# MCU.net
KiCad netlist of a schematic drawn in Altium Designer
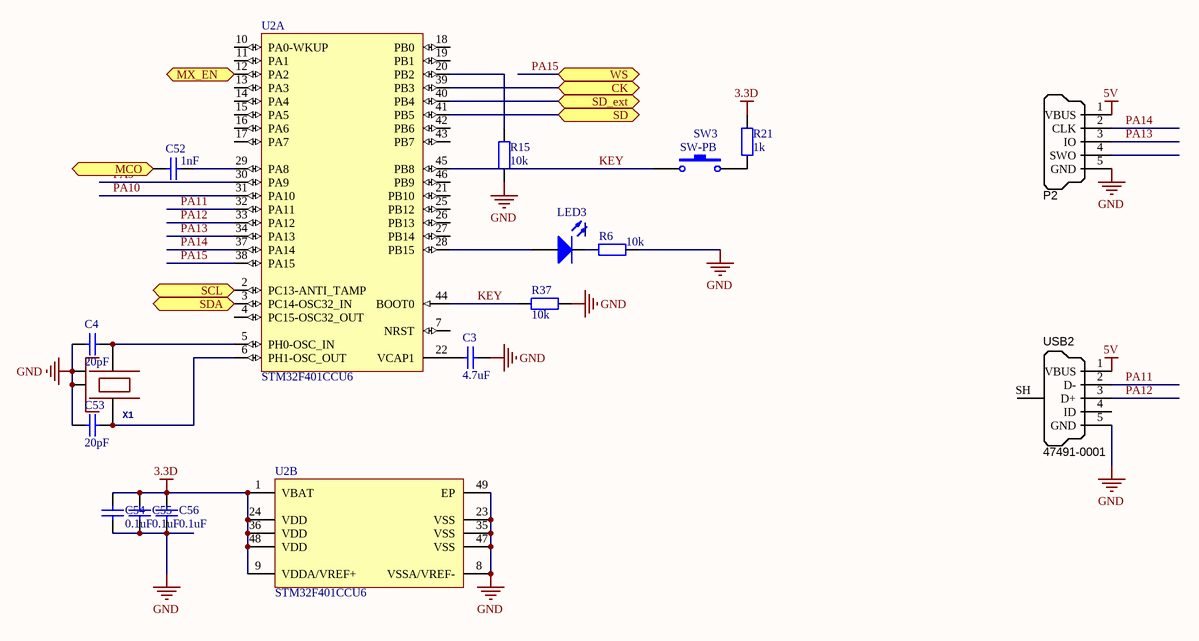
[diagram p0: MCU.SchDoc]

(export (version "E")
  (design (tool "Eeschema 10.0.6"))
  (components
    (comp (ref "C3")
      (value "4.7uF")
      (footprint "0603L")
      (description "Capacitor")
      (fields (field (name "Comment") "Cap") (field (name "PUBLISHER") "Altium Limited"))
      (libsource (lib "RTC6705") (part "Cap"))
    )
    (comp (ref "C4")
      (value "20pF")
      (footprint "0402")
      (description "Capacitor")
      (fields (field (name "Comment") "Cap") (field (name "PUBLISHER") "Altium Limited"))
      (libsource (lib "RTC6705") (part "Cap"))
    )
    (comp (ref "C52")
      (value "1nF")
      (footprint "0402")
      (description "Capacitor")
      (libsource (lib "RTC6705") (part "Cap"))
    )
    (comp (ref "C53")
      (value "20pF")
      (footprint "0402")
      (description "Capacitor")
      (fields (field (name "Comment") "Cap") (field (name "PUBLISHER") "Altium Limited"))
      (libsource (lib "RTC6705") (part "Cap"))
    )
    (comp (ref "C54")
      (value "0.1uF")
      (footprint "0402")
      (description "Capacitor")
      (fields (field (name "Comment") "Cap") (field (name "PUBLISHER") "Altium Limited"))
      (libsource (lib "RTC6705") (part "Cap"))
    )
    (comp (ref "C55")
      (value "0.1uF")
      (footprint "0402")
      (description "Capacitor")
      (fields (field (name "Comment") "Cap") (field (name "PUBLISHER") "Altium Limited"))
      (libsource (lib "RTC6705") (part "Cap"))
    )
    (comp (ref "C56")
      (value "0.1uF")
      (footprint "0402")
      (description "Capacitor")
      (fields (field (name "Comment") "Cap") (field (name "PUBLISHER") "Altium Limited"))
      (libsource (lib "RTC6705") (part "Cap"))
    )
    (comp (ref "LED3")
      (value "LED0")
      (footprint "0603")
      (description "Typical INFRARED GaAs LED")
      (fields (field (name "PUBLISHER") "Altium Limited"))
      (libsource (lib "Miscellaneous Devices") (part "LED0"))
    )
    (comp (ref "P2")
      (value "SWD_MicroUSB")
      (footprint "MICRO-YZX")
      (description "Connector SMD USB Micro Type B middle mount")
      (libsource (lib "sch") (part "SWD_MicroUSB"))
    )
    (comp (ref "R6")
      (value "10k")
      (footprint "0402")
      (description "Resistor")
      (fields (field (name "PUBLISHER") "Altium Limited"))
      (libsource (lib "Miscellaneous Devices") (part "Res2"))
    )
    (comp (ref "R15")
      (value "10k")
      (footprint "0402")
      (description "Resistor")
      (fields (field (name "PUBLISHER") "Altium Limited"))
      (libsource (lib "") (part "Res2_1"))
    )
    (comp (ref "R21")
      (value "1k")
      (footprint "0402")
      (description "Resistor")
      (fields (field (name "PUBLISHER") "Altium Limited"))
      (libsource (lib "") (part "Res2_2"))
    )
    (comp (ref "R37")
      (value "10k")
      (footprint "0402")
      (description "Resistor")
      (fields (field (name "Comment") "Res2") (field (name "PUBLISHER") "Altium Limited"))
      (libsource (lib "RTC6705") (part "Res2"))
    )
    (comp (ref "SW3")
      (value "SW-PB")
      (footprint "SW3x4")
      (description "Switch")
      (fields (field (name "PUBLISHER") "Altium Limited"))
      (libsource (lib "Miscellaneous Devices") (part "SW-PB"))
    )
    (comp (ref "U2")
      (value "STM32F401CCU6")
      (footprint "STM-UFQFPN48_N")
      (fields (field (name "MANUFACTURER") "STMicroelectronics"))
      (libsource (lib "STMicroelectronics STM32 F4") (part "STM32F401CCU6"))
    )
    (comp (ref "USB2")
      (value "USB Micro Type B")
      (footprint "MICRO-YZX")
      (description "Connector SMD USB Micro Type B middle mount")
      (fields (field (name "MANUFACTURER PART NUMBER 1") "47491-0001"))
      (libsource (lib "PBL - Connectors") (part "USB_Micro_TypeB"))
    )
    (comp (ref "X1")
      (value "24.000 KHz 3.2x2.5mm 8-10pf")
      (footprint "OSCILLATOR-2.5x2.0")
      (description "Crystal Oscillator in 3.2x2.5 SMD")
      (libsource (lib "pixhawk2") (part "OSCILLATOR-3.2X2.5"))
    )
  )
  (nets
    (net (code "1") (name "/CK") (class "Default")
      (node (ref "U2") (pin "39") (pinfunction "PB3_39") (pintype "bidirectional"))
    )
    (net (code "2") (name "/KEY") (class "Default")
      (node (ref "R37") (pin "1") (pinfunction "1_1") (pintype "passive"))
      (node (ref "SW3") (pin "1") (pinfunction "1_1") (pintype "passive"))
      (node (ref "U2") (pin "44") (pinfunction "BOOT0_44") (pintype "input"))
      (node (ref "U2") (pin "45") (pinfunction "PB8_45") (pintype "bidirectional"))
    )
    (net (code "3") (name "/MCO") (class "Default")
      (node (ref "C52") (pin "1") (pinfunction "1_1") (pintype "passive"))
    )
    (net (code "4") (name "/MX_EN") (class "Default")
      (node (ref "U2") (pin "12") (pinfunction "PA2_12") (pintype "bidirectional"))
    )
    (net (code "5") (name "/PA9") (class "Default")
      (node (ref "U2") (pin "30") (pinfunction "PA9_30") (pintype "bidirectional"))
    )
    (net (code "6") (name "/PA10") (class "Default")
      (node (ref "U2") (pin "31") (pinfunction "PA10_31") (pintype "bidirectional"))
    )
    (net (code "7") (name "/PA11") (class "Default")
      (node (ref "U2") (pin "32") (pinfunction "PA11_32") (pintype "bidirectional"))
      (node (ref "USB2") (pin "2") (pinfunction "D-_2") (pintype "passive"))
    )
    (net (code "8") (name "/PA12") (class "Default")
      (node (ref "U2") (pin "33") (pinfunction "PA12_33") (pintype "bidirectional"))
      (node (ref "USB2") (pin "3") (pinfunction "D+_3") (pintype "passive"))
    )
    (net (code "9") (name "/PA13") (class "Default")
      (node (ref "P2") (pin "3") (pinfunction "IO_3") (pintype "passive"))
      (node (ref "U2") (pin "34") (pinfunction "PA13_34") (pintype "bidirectional"))
    )
    (net (code "10") (name "/PA14") (class "Default")
      (node (ref "P2") (pin "2") (pinfunction "CLK_2") (pintype "passive"))
      (node (ref "U2") (pin "37") (pinfunction "PA14_37") (pintype "bidirectional"))
    )
    (net (code "11") (name "/PA15") (class "Default")
      (node (ref "U2") (pin "38") (pinfunction "PA15_38") (pintype "bidirectional"))
    )
    (net (code "12") (name "/SCL") (class "Default")
      (node (ref "U2") (pin "2") (pinfunction "PC13-ANTI_TAMP_2") (pintype "bidirectional"))
    )
    (net (code "13") (name "/SD") (class "Default")
      (node (ref "U2") (pin "41") (pinfunction "PB5_41") (pintype "bidirectional"))
    )
    (net (code "14") (name "/SDA") (class "Default")
      (node (ref "U2") (pin "3") (pinfunction "PC14-OSC32_IN_3") (pintype "bidirectional"))
    )
    (net (code "15") (name "/SD_ext") (class "Default")
      (node (ref "U2") (pin "40") (pinfunction "PB4_40") (pintype "bidirectional"))
    )
    (net (code "16") (name "3.3D") (class "Default")
      (node (ref "C54") (pin "2") (pinfunction "2_2") (pintype "passive"))
      (node (ref "C55") (pin "2") (pinfunction "2_2") (pintype "passive"))
      (node (ref "C56") (pin "2") (pinfunction "2_2") (pintype "passive"))
      (node (ref "R21") (pin "2") (pinfunction "2_2") (pintype "passive"))
      (node (ref "U2") (pin "1") (pinfunction "VBAT_1") (pintype "power_in"))
      (node (ref "U2") (pin "24") (pinfunction "VDD_24") (pintype "power_in"))
      (node (ref "U2") (pin "36") (pinfunction "VDD_36") (pintype "power_in"))
      (node (ref "U2") (pin "48") (pinfunction "VDD_48") (pintype "power_in"))
      (node (ref "U2") (pin "9") (pinfunction "VDDA/VREF+_9") (pintype "power_in"))
    )
    (net (code "17") (name "5V") (class "Default")
      (node (ref "P2") (pin "1") (pinfunction "VBUS_1") (pintype "passive"))
      (node (ref "USB2") (pin "1") (pinfunction "VBUS_1") (pintype "passive"))
    )
    (net (code "18") (name "GND") (class "Default")
      (node (ref "C3") (pin "1") (pinfunction "1_1") (pintype "passive"))
      (node (ref "C4") (pin "1") (pinfunction "1_1") (pintype "passive"))
      (node (ref "C53") (pin "1") (pinfunction "1_1") (pintype "passive"))
      (node (ref "C54") (pin "1") (pinfunction "1_1") (pintype "passive"))
      (node (ref "C55") (pin "1") (pinfunction "1_1") (pintype "passive"))
      (node (ref "C56") (pin "1") (pinfunction "1_1") (pintype "passive"))
      (node (ref "P2") (pin "5") (pinfunction "GND_5") (pintype "passive"))
      (node (ref "R15") (pin "2") (pinfunction "2_2") (pintype "passive"))
      (node (ref "R37") (pin "2") (pinfunction "2_2") (pintype "passive"))
      (node (ref "R6") (pin "2") (pinfunction "2_2") (pintype "passive"))
      (node (ref "U2") (pin "23") (pinfunction "VSS_23") (pintype "power_in"))
      (node (ref "U2") (pin "35") (pinfunction "VSS_35") (pintype "power_in"))
      (node (ref "U2") (pin "47") (pinfunction "VSS_47") (pintype "power_in"))
      (node (ref "U2") (pin "49") (pinfunction "EP_49") (pintype "power_in"))
      (node (ref "U2") (pin "8") (pinfunction "VSSA/VREF-_8") (pintype "power_in"))
      (node (ref "USB2") (pin "5") (pinfunction "GND_5") (pintype "passive"))
      (node (ref "X1") (pin "2") (pinfunction "NC_2_2") (pintype "open_emitter"))
      (node (ref "X1") (pin "4") (pinfunction "NC_4_4") (pintype "open_emitter"))
    )
    (net (code "19") (name "Net-(LED3-A)") (class "Default")
      (node (ref "LED3") (pin "1") (pinfunction "A_1") (pintype "passive"))
      (node (ref "U2") (pin "28") (pinfunction "PB15_28") (pintype "bidirectional"))
    )
    (net (code "20") (name "Net-(LED3-K)") (class "Default")
      (node (ref "LED3") (pin "2") (pinfunction "K_2") (pintype "passive"))
      (node (ref "R6") (pin "1") (pinfunction "1_1") (pintype "passive"))
    )
    (net (code "21") (name "Net-(R21-Pad1)") (class "Default")
      (node (ref "R21") (pin "1") (pinfunction "1_1") (pintype "passive"))
      (node (ref "SW3") (pin "2") (pinfunction "2_2") (pintype "passive"))
    )
    (net (code "22") (name "Net-(U2A-PA8)") (class "Default")
      (node (ref "C52") (pin "2") (pinfunction "2_2") (pintype "passive"))
      (node (ref "U2") (pin "29") (pinfunction "PA8_29") (pintype "bidirectional"))
    )
    (net (code "23") (name "Net-(U2A-PB2)") (class "Default")
      (node (ref "R15") (pin "1") (pinfunction "1_1") (pintype "passive"))
      (node (ref "U2") (pin "20") (pinfunction "PB2_20") (pintype "bidirectional"))
    )
    (net (code "24") (name "Net-(U2A-PH0-OSC_IN)") (class "Default")
      (node (ref "C4") (pin "2") (pinfunction "2_2") (pintype "passive"))
      (node (ref "U2") (pin "5") (pinfunction "PH0-OSC_IN_5") (pintype "bidirectional"))
      (node (ref "X1") (pin "1") (pinfunction "1_1") (pintype "passive"))
    )
    (net (code "25") (name "Net-(U2A-PH1-OSC_OUT)") (class "Default")
      (node (ref "C53") (pin "2") (pinfunction "2_2") (pintype "passive"))
      (node (ref "U2") (pin "6") (pinfunction "PH1-OSC_OUT_6") (pintype "bidirectional"))
      (node (ref "X1") (pin "3") (pinfunction "3_3") (pintype "passive"))
    )
    (net (code "26") (name "Net-(U2A-VCAP1)") (class "Default")
      (node (ref "C3") (pin "2") (pinfunction "2_2") (pintype "passive"))
      (node (ref "U2") (pin "22") (pinfunction "VCAP1_22") (pintype "power_in"))
    )
    (net (code "27") (name "unconnected-(P2-SWO-Pad4)") (class "Default")
      (node (ref "P2") (pin "4") (pinfunction "SWO_4") (pintype "passive"))
    )
    (net (code "28") (name "unconnected-(U2A-NRST-Pad7)") (class "Default")
      (node (ref "U2") (pin "7") (pinfunction "NRST_7") (pintype "bidirectional"))
    )
    (net (code "29") (name "unconnected-(U2A-PA0-WKUP-Pad10)") (class "Default")
      (node (ref "U2") (pin "10") (pinfunction "PA0-WKUP_10") (pintype "bidirectional"))
    )
    (net (code "30") (name "unconnected-(U2A-PA1-Pad11)") (class "Default")
      (node (ref "U2") (pin "11") (pinfunction "PA1_11") (pintype "bidirectional"))
    )
    (net (code "31") (name "unconnected-(U2A-PA3-Pad13)") (class "Default")
      (node (ref "U2") (pin "13") (pinfunction "PA3_13") (pintype "bidirectional"))
    )
    (net (code "32") (name "unconnected-(U2A-PA4-Pad14)") (class "Default")
      (node (ref "U2") (pin "14") (pinfunction "PA4_14") (pintype "bidirectional"))
    )
    (net (code "33") (name "unconnected-(U2A-PA5-Pad15)") (class "Default")
      (node (ref "U2") (pin "15") (pinfunction "PA5_15") (pintype "bidirectional"))
    )
    (net (code "34") (name "unconnected-(U2A-PA6-Pad16)") (class "Default")
      (node (ref "U2") (pin "16") (pinfunction "PA6_16") (pintype "bidirectional"))
    )
    (net (code "35") (name "unconnected-(U2A-PA7-Pad17)") (class "Default")
      (node (ref "U2") (pin "17") (pinfunction "PA7_17") (pintype "bidirectional"))
    )
    (net (code "36") (name "unconnected-(U2A-PB0-Pad18)") (class "Default")
      (node (ref "U2") (pin "18") (pinfunction "PB0_18") (pintype "bidirectional"))
    )
    (net (code "37") (name "unconnected-(U2A-PB1-Pad19)") (class "Default")
      (node (ref "U2") (pin "19") (pinfunction "PB1_19") (pintype "bidirectional"))
    )
    (net (code "38") (name "unconnected-(U2A-PB6-Pad42)") (class "Default")
      (node (ref "U2") (pin "42") (pinfunction "PB6_42") (pintype "bidirectional"))
    )
    (net (code "39") (name "unconnected-(U2A-PB7-Pad43)") (class "Default")
      (node (ref "U2") (pin "43") (pinfunction "PB7_43") (pintype "bidirectional"))
    )
    (net (code "40") (name "unconnected-(U2A-PB9-Pad46)") (class "Default")
      (node (ref "U2") (pin "46") (pinfunction "PB9_46") (pintype "bidirectional"))
    )
    (net (code "41") (name "unconnected-(U2A-PB10-Pad21)") (class "Default")
      (node (ref "U2") (pin "21") (pinfunction "PB10_21") (pintype "bidirectional"))
    )
    (net (code "42") (name "unconnected-(U2A-PB12-Pad25)") (class "Default")
      (node (ref "U2") (pin "25") (pinfunction "PB12_25") (pintype "bidirectional"))
    )
    (net (code "43") (name "unconnected-(U2A-PB13-Pad26)") (class "Default")
      (node (ref "U2") (pin "26") (pinfunction "PB13_26") (pintype "bidirectional"))
    )
    (net (code "44") (name "unconnected-(U2A-PB14-Pad27)") (class "Default")
      (node (ref "U2") (pin "27") (pinfunction "PB14_27") (pintype "bidirectional"))
    )
    (net (code "45") (name "unconnected-(U2A-PC15-OSC32_OUT-Pad4)") (class "Default")
      (node (ref "U2") (pin "4") (pinfunction "PC15-OSC32_OUT_4") (pintype "bidirectional"))
    )
    (net (code "46") (name "unconnected-(USB2-ID-Pad4)") (class "Default")
      (node (ref "USB2") (pin "4") (pinfunction "ID_4") (pintype "passive"))
    )
    (net (code "47") (name "unconnected-(USB2-Shell-PadSH)") (class "Default")
      (node (ref "USB2") (pin "SH") (pinfunction "Shell_SH") (pintype "passive"))
    )
  )
)
